# LPC_Rep.net
KiCad netlist of a schematic drawn in Altium Designer
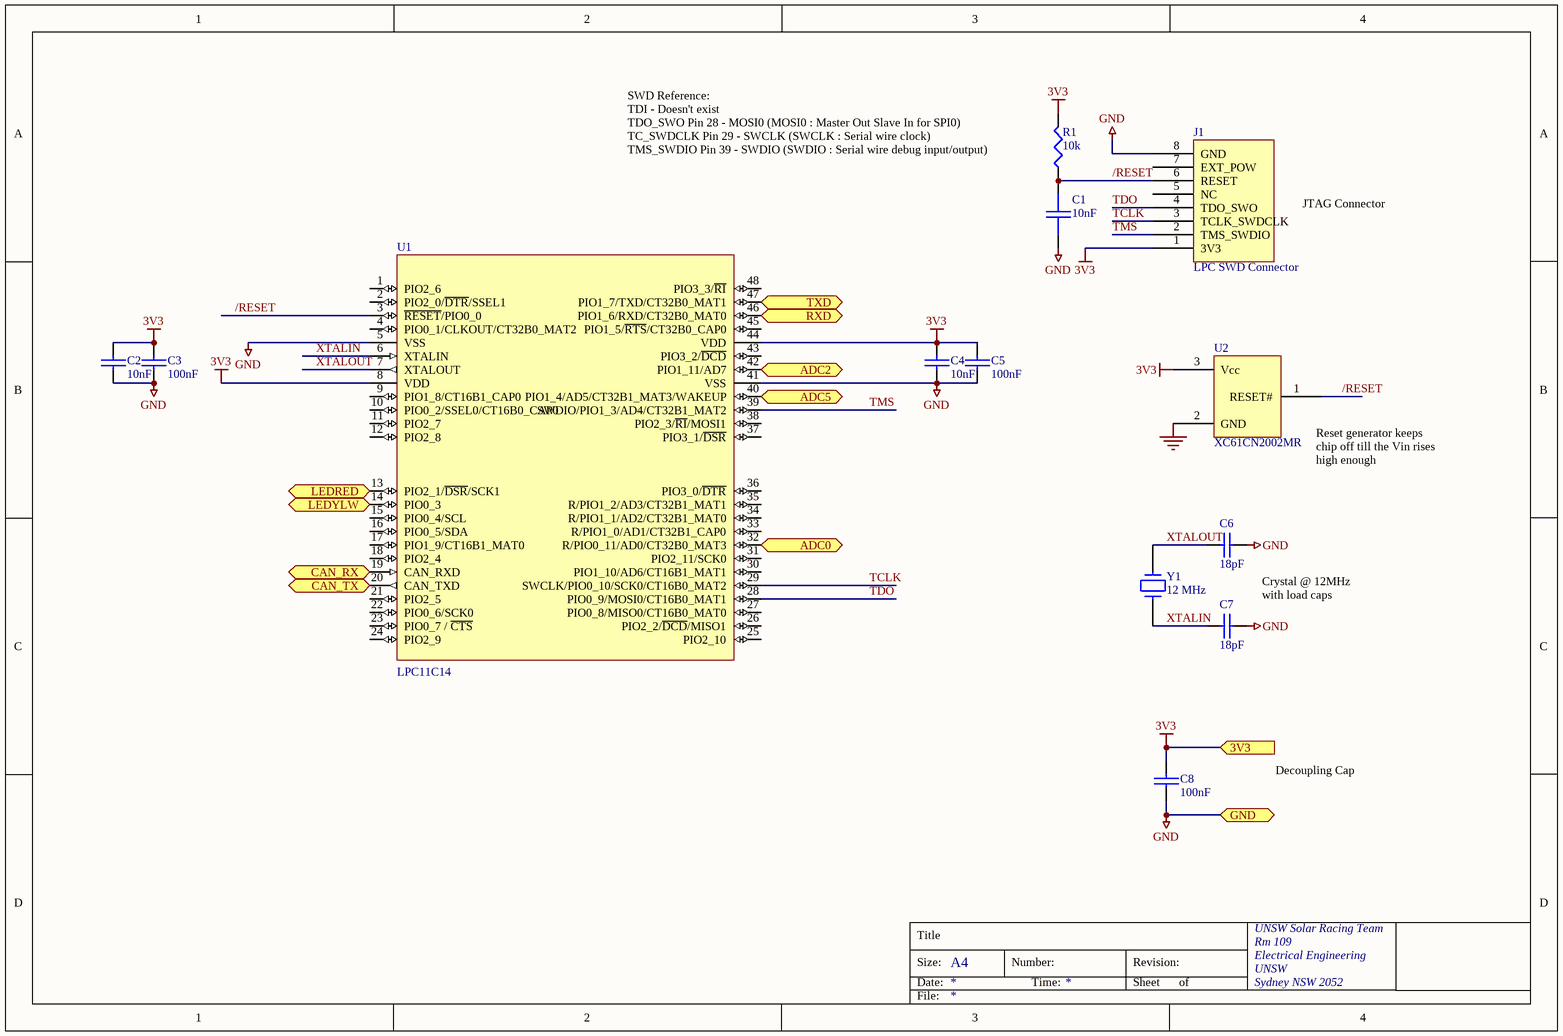
[diagram p0: LPC_Rep.SchDoc]

(export (version "E")
  (design (tool "Eeschema 10.0.6"))
  (components
    (comp (ref "C1")
      (value "10nF")
      (footprint "0603")
      (description "Capacitor")
      (libsource (lib "SunswiftLib20030312RR") (part "CAP"))
    )
    (comp (ref "C2")
      (value "10nF")
      (footprint "0603")
      (description "Capacitor")
      (libsource (lib "*") (part "CAP"))
    )
    (comp (ref "C3")
      (value "100nF")
      (footprint "0603")
      (description "Capacitor")
      (libsource (lib "*") (part "CAP"))
    )
    (comp (ref "C4")
      (value "10nF")
      (footprint "0603")
      (description "Capacitor")
      (libsource (lib "*") (part "CAP"))
    )
    (comp (ref "C5")
      (value "100nF")
      (footprint "0603")
      (description "Capacitor")
      (libsource (lib "*") (part "CAP"))
    )
    (comp (ref "C6")
      (value "18pF")
      (footprint "0603")
      (description "Capacitor")
      (libsource (lib "*") (part "CAP"))
    )
    (comp (ref "C7")
      (value "18pF")
      (footprint "0603")
      (description "Capacitor")
      (libsource (lib "*") (part "CAP"))
    )
    (comp (ref "C8")
      (value "100nF")
      (footprint "0603")
      (description "Capacitor")
      (libsource (lib "*") (part "CAP"))
    )
    (comp (ref "J1")
      (value "LPC SWD Connector")
      (footprint "Footprint:IDC8")
      (libsource (lib "2009_BatteryMaster") (part "LPCLink_Connector"))
    )
    (comp (ref "R1")
      (value "10k")
      (footprint "0603")
      (description "Resistor")
      (libsource (lib "SunswiftLib20030312RR") (part "RES1"))
    )
    (comp (ref "U1")
      (value "LPC11C14")
      (footprint "TSQFP50P900X900-48N")
      (libsource (lib "LPC") (part "LPC11C14_Full"))
    )
    (comp (ref "U2")
      (value "XC61CN2002MR")
      (footprint "SOT23-3")
      (description "SOT23 reset generator")
      (libsource (lib "*") (part "XC61F"))
    )
    (comp (ref "Y1")
      (value "12 MHz")
      (footprint "HC49/4H")
      (description "Crystal")
      (libsource (lib "*") (part "CRYSTAL"))
    )
  )
  (nets
    (net (code "1") (name "/ADC0") (class "Default")
      (node (ref "U1") (pin "32") (pinfunction "R/PIO0_11/AD0/CT32B0_MAT3_32") (pintype "bidirectional"))
    )
    (net (code "2") (name "/ADC2") (class "Default")
      (node (ref "U1") (pin "42") (pinfunction "PIO1_11/AD7_42") (pintype "bidirectional"))
    )
    (net (code "3") (name "/ADC5") (class "Default")
      (node (ref "U1") (pin "40") (pinfunction "PIO1_4/AD5/CT32B1_MAT3/WAKEUP_40") (pintype "bidirectional"))
    )
    (net (code "4") (name "/CAN_RX") (class "Default")
      (node (ref "U1") (pin "19") (pinfunction "CAN_RXD_19") (pintype "input"))
    )
    (net (code "5") (name "/CAN_TX") (class "Default")
      (node (ref "U1") (pin "20") (pinfunction "CAN_TXD_20") (pintype "output"))
    )
    (net (code "6") (name "/LEDRED") (class "Default")
      (node (ref "U1") (pin "13") (pinfunction "PIO2_1/~{DSR}/SCK1_13") (pintype "bidirectional"))
    )
    (net (code "7") (name "/LEDYLW") (class "Default")
      (node (ref "U1") (pin "14") (pinfunction "PIO0_3_14") (pintype "bidirectional"))
    )
    (net (code "8") (name "/RXD") (class "Default")
      (node (ref "U1") (pin "46") (pinfunction "PIO1_6/RXD/CT32B0_MAT0_46") (pintype "bidirectional"))
    )
    (net (code "9") (name "/TCLK") (class "Default")
      (node (ref "J1") (pin "3") (pinfunction "TCLK_SWDCLK_3") (pintype "passive"))
      (node (ref "U1") (pin "29") (pinfunction "SWCLK/PIO0_10/SCK0/CT16B0_MAT2_29") (pintype "bidirectional"))
    )
    (net (code "10") (name "/TDO") (class "Default")
      (node (ref "J1") (pin "4") (pinfunction "TDO_SWO_4") (pintype "passive"))
      (node (ref "U1") (pin "28") (pinfunction "PIO0_9/MOSI0/CT16B0_MAT1_28") (pintype "bidirectional"))
    )
    (net (code "11") (name "/TMS") (class "Default")
      (node (ref "J1") (pin "2") (pinfunction "TMS_SWDIO_2") (pintype "passive"))
      (node (ref "U1") (pin "39") (pinfunction "SWDIO/PIO1_3/AD4/CT32B1_MAT2_39") (pintype "bidirectional"))
    )
    (net (code "12") (name "/TXD") (class "Default")
      (node (ref "U1") (pin "47") (pinfunction "PIO1_7/TXD/CT32B0_MAT1_47") (pintype "bidirectional"))
    )
    (net (code "13") (name "/XTALIN") (class "Default")
      (node (ref "C7") (pin "1") (pinfunction "1_1") (pintype "passive"))
      (node (ref "U1") (pin "6") (pinfunction "XTALIN_6") (pintype "input"))
      (node (ref "Y1") (pin "1") (pinfunction "1_1") (pintype "passive"))
    )
    (net (code "14") (name "/XTALOUT") (class "Default")
      (node (ref "C6") (pin "1") (pinfunction "1_1") (pintype "passive"))
      (node (ref "U1") (pin "7") (pinfunction "XTALOUT_7") (pintype "output"))
      (node (ref "Y1") (pin "2") (pinfunction "2_2") (pintype "passive"))
    )
    (net (code "15") (name "/{slash}RESET") (class "Default")
      (node (ref "C1") (pin "1") (pinfunction "1_1") (pintype "passive"))
      (node (ref "J1") (pin "6") (pinfunction "RESET_6") (pintype "passive"))
      (node (ref "R1") (pin "1") (pinfunction "1_1") (pintype "passive"))
      (node (ref "U1") (pin "3") (pinfunction "~{RESET}/PIO0_0_3") (pintype "bidirectional"))
      (node (ref "U2") (pin "1") (pinfunction "RESET#_1") (pintype "passive"))
    )
    (net (code "16") (name "3V3") (class "Default")
      (node (ref "C2") (pin "2") (pinfunction "2_2") (pintype "passive"))
      (node (ref "C3") (pin "2") (pinfunction "2_2") (pintype "passive"))
      (node (ref "C4") (pin "2") (pinfunction "2_2") (pintype "passive"))
      (node (ref "C5") (pin "2") (pinfunction "2_2") (pintype "passive"))
      (node (ref "C8") (pin "1") (pinfunction "1_1") (pintype "passive"))
      (node (ref "J1") (pin "1") (pinfunction "3V3_1") (pintype "passive"))
      (node (ref "R1") (pin "2") (pinfunction "2_2") (pintype "passive"))
      (node (ref "U1") (pin "44") (pinfunction "VDD_44") (pintype "power_in"))
      (node (ref "U1") (pin "8") (pinfunction "VDD_8") (pintype "power_in"))
      (node (ref "U2") (pin "3") (pinfunction "Vcc_3") (pintype "passive"))
    )
    (net (code "17") (name "GND") (class "Default")
      (node (ref "C1") (pin "2") (pinfunction "2_2") (pintype "passive"))
      (node (ref "C2") (pin "1") (pinfunction "1_1") (pintype "passive"))
      (node (ref "C3") (pin "1") (pinfunction "1_1") (pintype "passive"))
      (node (ref "C4") (pin "1") (pinfunction "1_1") (pintype "passive"))
      (node (ref "C5") (pin "1") (pinfunction "1_1") (pintype "passive"))
      (node (ref "C6") (pin "2") (pinfunction "2_2") (pintype "passive"))
      (node (ref "C7") (pin "2") (pinfunction "2_2") (pintype "passive"))
      (node (ref "C8") (pin "2") (pinfunction "2_2") (pintype "passive"))
      (node (ref "J1") (pin "8") (pinfunction "GND_8") (pintype "passive"))
      (node (ref "U1") (pin "41") (pinfunction "VSS_41") (pintype "power_in"))
      (node (ref "U1") (pin "5") (pinfunction "VSS_5") (pintype "power_in"))
      (node (ref "U2") (pin "2") (pinfunction "GND_2") (pintype "passive"))
    )
    (net (code "18") (name "unconnected-(J1-EXT_POW-Pad7)") (class "Default")
      (node (ref "J1") (pin "7") (pinfunction "EXT_POW_7") (pintype "passive"))
    )
    (net (code "19") (name "unconnected-(J1-NC-Pad5)") (class "Default")
      (node (ref "J1") (pin "5") (pinfunction "NC_5") (pintype "passive"))
    )
    (net (code "20") (name "unconnected-(U1-PIO0_1{slash}CLKOUT{slash}CT32B0_MAT2-Pad4)") (class "Default")
      (node (ref "U1") (pin "4") (pinfunction "PIO0_1/CLKOUT/CT32B0_MAT2_4") (pintype "bidirectional"))
    )
    (net (code "21") (name "unconnected-(U1-PIO0_2{slash}SSEL0{slash}CT16B0_CAP0-Pad10)") (class "Default")
      (node (ref "U1") (pin "10") (pinfunction "PIO0_2/SSEL0/CT16B0_CAP0_10") (pintype "bidirectional"))
    )
    (net (code "22") (name "unconnected-(U1-PIO0_4{slash}SCL-Pad15)") (class "Default")
      (node (ref "U1") (pin "15") (pinfunction "PIO0_4/SCL_15") (pintype "bidirectional"))
    )
    (net (code "23") (name "unconnected-(U1-PIO0_5{slash}SDA-Pad16)") (class "Default")
      (node (ref "U1") (pin "16") (pinfunction "PIO0_5/SDA_16") (pintype "bidirectional"))
    )
    (net (code "24") (name "unconnected-(U1-PIO0_6{slash}SCK0-Pad22)") (class "Default")
      (node (ref "U1") (pin "22") (pinfunction "PIO0_6/SCK0_22") (pintype "bidirectional"))
    )
    (net (code "25") (name "unconnected-(U1-PIO0_7_{slash}_~{CTS}-Pad23)") (class "Default")
      (node (ref "U1") (pin "23") (pinfunction "PIO0_7_/_~{CTS}_23") (pintype "bidirectional"))
    )
    (net (code "26") (name "unconnected-(U1-PIO0_8{slash}MISO0{slash}CT16B0_MAT0-Pad27)") (class "Default")
      (node (ref "U1") (pin "27") (pinfunction "PIO0_8/MISO0/CT16B0_MAT0_27") (pintype "bidirectional"))
    )
    (net (code "27") (name "unconnected-(U1-PIO1_5{slash}~{RTS}{slash}CT32B0_CAP0-Pad45)") (class "Default")
      (node (ref "U1") (pin "45") (pinfunction "PIO1_5/~{RTS}/CT32B0_CAP0_45") (pintype "bidirectional"))
    )
    (net (code "28") (name "unconnected-(U1-PIO1_8{slash}CT16B1_CAP0-Pad9)") (class "Default")
      (node (ref "U1") (pin "9") (pinfunction "PIO1_8/CT16B1_CAP0_9") (pintype "bidirectional"))
    )
    (net (code "29") (name "unconnected-(U1-PIO1_9{slash}CT16B1_MAT0-Pad17)") (class "Default")
      (node (ref "U1") (pin "17") (pinfunction "PIO1_9/CT16B1_MAT0_17") (pintype "bidirectional"))
    )
    (net (code "30") (name "unconnected-(U1-PIO1_10{slash}AD6{slash}CT16B1_MAT1-Pad30)") (class "Default")
      (node (ref "U1") (pin "30") (pinfunction "PIO1_10/AD6/CT16B1_MAT1_30") (pintype "bidirectional"))
    )
    (net (code "31") (name "unconnected-(U1-PIO2_0{slash}~{DTR}{slash}SSEL1-Pad2)") (class "Default")
      (node (ref "U1") (pin "2") (pinfunction "PIO2_0/~{DTR}/SSEL1_2") (pintype "bidirectional"))
    )
    (net (code "32") (name "unconnected-(U1-PIO2_2{slash}~{DCD}{slash}MISO1-Pad26)") (class "Default")
      (node (ref "U1") (pin "26") (pinfunction "PIO2_2/~{DCD}/MISO1_26") (pintype "bidirectional"))
    )
    (net (code "33") (name "unconnected-(U1-PIO2_3{slash}~{RI}{slash}MOSI1-Pad38)") (class "Default")
      (node (ref "U1") (pin "38") (pinfunction "PIO2_3/~{RI}/MOSI1_38") (pintype "bidirectional"))
    )
    (net (code "34") (name "unconnected-(U1-PIO2_4-Pad18)") (class "Default")
      (node (ref "U1") (pin "18") (pinfunction "PIO2_4_18") (pintype "bidirectional"))
    )
    (net (code "35") (name "unconnected-(U1-PIO2_5-Pad21)") (class "Default")
      (node (ref "U1") (pin "21") (pinfunction "PIO2_5_21") (pintype "bidirectional"))
    )
    (net (code "36") (name "unconnected-(U1-PIO2_6-Pad1)") (class "Default")
      (node (ref "U1") (pin "1") (pinfunction "PIO2_6_1") (pintype "bidirectional"))
    )
    (net (code "37") (name "unconnected-(U1-PIO2_7-Pad11)") (class "Default")
      (node (ref "U1") (pin "11") (pinfunction "PIO2_7_11") (pintype "bidirectional"))
    )
    (net (code "38") (name "unconnected-(U1-PIO2_8-Pad12)") (class "Default")
      (node (ref "U1") (pin "12") (pinfunction "PIO2_8_12") (pintype "bidirectional"))
    )
    (net (code "39") (name "unconnected-(U1-PIO2_9-Pad24)") (class "Default")
      (node (ref "U1") (pin "24") (pinfunction "PIO2_9_24") (pintype "bidirectional"))
    )
    (net (code "40") (name "unconnected-(U1-PIO2_10-Pad25)") (class "Default")
      (node (ref "U1") (pin "25") (pinfunction "PIO2_10_25") (pintype "bidirectional"))
    )
    (net (code "41") (name "unconnected-(U1-PIO2_11{slash}SCK0-Pad31)") (class "Default")
      (node (ref "U1") (pin "31") (pinfunction "PIO2_11/SCK0_31") (pintype "bidirectional"))
    )
    (net (code "42") (name "unconnected-(U1-PIO3_0{slash}~{DTR}-Pad36)") (class "Default")
      (node (ref "U1") (pin "36") (pinfunction "PIO3_0/~{DTR}_36") (pintype "bidirectional"))
    )
    (net (code "43") (name "unconnected-(U1-PIO3_1{slash}~{DSR}-Pad37)") (class "Default")
      (node (ref "U1") (pin "37") (pinfunction "PIO3_1/~{DSR}_37") (pintype "bidirectional"))
    )
    (net (code "44") (name "unconnected-(U1-PIO3_2{slash}~{DCD}-Pad43)") (class "Default")
      (node (ref "U1") (pin "43") (pinfunction "PIO3_2/~{DCD}_43") (pintype "bidirectional"))
    )
    (net (code "45") (name "unconnected-(U1-PIO3_3{slash}~{RI}-Pad48)") (class "Default")
      (node (ref "U1") (pin "48") (pinfunction "PIO3_3/~{RI}_48") (pintype "bidirectional"))
    )
    (net (code "46") (name "unconnected-(U1-R{slash}PIO1_0{slash}AD1{slash}CT32B1_CAP0-Pad33)") (class "Default")
      (node (ref "U1") (pin "33") (pinfunction "R/PIO1_0/AD1/CT32B1_CAP0_33") (pintype "bidirectional"))
    )
    (net (code "47") (name "unconnected-(U1-R{slash}PIO1_1{slash}AD2{slash}CT32B1_MAT0-Pad34)") (class "Default")
      (node (ref "U1") (pin "34") (pinfunction "R/PIO1_1/AD2/CT32B1_MAT0_34") (pintype "bidirectional"))
    )
    (net (code "48") (name "unconnected-(U1-R{slash}PIO1_2{slash}AD3{slash}CT32B1_MAT1-Pad35)") (class "Default")
      (node (ref "U1") (pin "35") (pinfunction "R/PIO1_2/AD3/CT32B1_MAT1_35") (pintype "bidirectional"))
    )
  )
)
